# 11_MICROSD.net
KiCad netlist of a schematic drawn in Altium Designer
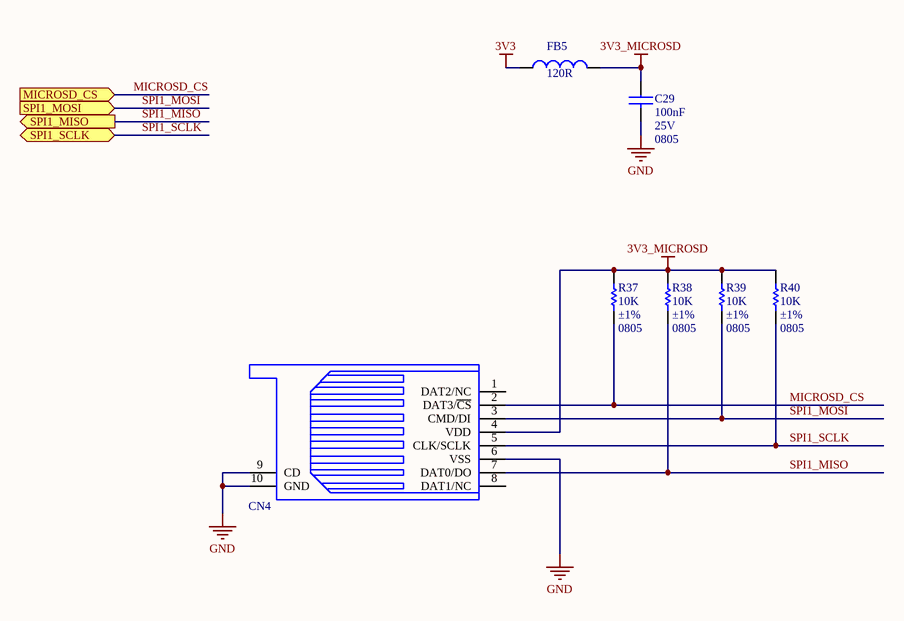
[diagram p0: 11.MICROSD.SchDoc]

(export (version "E")
  (design (tool "Eeschema 10.0.6"))
  (components
    (comp (ref "C29")
      (value "CAP_NP")
      (footprint "CAPC2012X100N_EIA0805")
      (description "CAP CER 0.1UF 25V X7R 0805")
      (fields
        (field (name "PART NUMBER") "SCAP00300093")
        (field (name "CAPACITANCE") "100nF")
        (field (name "TOLERANCE") "±10%")
        (field (name "VOLTAGE - RATED") "25V")
        (field (name "PACKAGE / CASE") "0805")
      )
      (libsource (lib "ComponentDatabase") (part "CAP_NP"))
    )
    (comp (ref "CN4")
      (value "MICRO-SD")
      (footprint "MOLEX_0472192001")
      (description "CONN MICRO SD CARD HINGED TYPE")
      (fields (field (name "PART NUMBER") "SCON00095") (field (name "MANUFACTURER") "Molex, LLC"))
      (libsource (lib "ComponentDatabase") (part "MICRO-SD"))
    )
    (comp (ref "FB5")
      (value "BEAD")
      (footprint "FILC2012X100N_EIA0805")
      (description "FERRITE CHIP POWER 120 OHM SMD")
      (fields
        (field (name "PART NUMBER") "SFIL00005")
        (field (name "IMPEDANCE") "120R")
        (field (name "MANUFACTURER") "Laird-Signal Integrity Products")
      )
      (libsource (lib "ComponentDatabase") (part "BEAD"))
    )
    (comp (ref "R37")
      (value "10K")
      (footprint "RESC2013X65N_EIA0805")
      (description "RES SMD 10K OHM 1% 1/8W 0805")
      (fields
        (field (name "PART NUMBER") "SRES03010098")
        (field (name "TOLERANCE") "±1%")
        (field (name "PACKAGE / CASE") "0805")
        (field (name "MANUFACTURER") "Yageo")
      )
      (libsource (lib "ComponentDatabase") (part "RES"))
    )
    (comp (ref "R38")
      (value "10K")
      (footprint "RESC2013X65N_EIA0805")
      (description "RES SMD 10K OHM 1% 1/8W 0805")
      (fields
        (field (name "PART NUMBER") "SRES03010098")
        (field (name "TOLERANCE") "±1%")
        (field (name "PACKAGE / CASE") "0805")
        (field (name "MANUFACTURER") "Yageo")
      )
      (libsource (lib "ComponentDatabase") (part "RES"))
    )
    (comp (ref "R39")
      (value "10K")
      (footprint "RESC2013X65N_EIA0805")
      (description "RES SMD 10K OHM 1% 1/8W 0805")
      (fields
        (field (name "PART NUMBER") "SRES03010098")
        (field (name "TOLERANCE") "±1%")
        (field (name "PACKAGE / CASE") "0805")
        (field (name "MANUFACTURER") "Yageo")
      )
      (libsource (lib "ComponentDatabase") (part "RES"))
    )
    (comp (ref "R40")
      (value "10K")
      (footprint "RESC2013X65N_EIA0805")
      (description "RES SMD 10K OHM 1% 1/8W 0805")
      (fields
        (field (name "PART NUMBER") "SRES03010098")
        (field (name "TOLERANCE") "±1%")
        (field (name "PACKAGE / CASE") "0805")
        (field (name "MANUFACTURER") "Yageo")
      )
      (libsource (lib "ComponentDatabase") (part "RES"))
    )
  )
  (nets
    (net (code "1") (name "/MICROSD_CS") (class "Default")
      (node (ref "CN4") (pin "2") (pinfunction "DAT3/~{CS}_2") (pintype "passive"))
      (node (ref "R37") (pin "2") (pinfunction "2_2") (pintype "passive"))
    )
    (net (code "2") (name "/SPI1_MISO") (class "Default")
      (node (ref "CN4") (pin "7") (pinfunction "DAT0/DO_7") (pintype "passive"))
      (node (ref "R38") (pin "2") (pinfunction "2_2") (pintype "passive"))
    )
    (net (code "3") (name "/SPI1_MOSI") (class "Default")
      (node (ref "CN4") (pin "3") (pinfunction "CMD/DI_3") (pintype "passive"))
      (node (ref "R39") (pin "2") (pinfunction "2_2") (pintype "passive"))
    )
    (net (code "4") (name "/SPI1_SCLK") (class "Default")
      (node (ref "CN4") (pin "5") (pinfunction "CLK/SCLK_5") (pintype "passive"))
      (node (ref "R40") (pin "2") (pinfunction "2_2") (pintype "passive"))
    )
    (net (code "5") (name "3V3") (class "Default")
      (node (ref "FB5") (pin "1") (pinfunction "1_1") (pintype "passive"))
    )
    (net (code "6") (name "3V3_MICROSD") (class "Default")
      (node (ref "C29") (pin "1") (pinfunction "1_1") (pintype "passive"))
      (node (ref "CN4") (pin "4") (pinfunction "VDD_4") (pintype "passive"))
      (node (ref "FB5") (pin "2") (pinfunction "2_2") (pintype "passive"))
      (node (ref "R37") (pin "1") (pinfunction "1_1") (pintype "passive"))
      (node (ref "R38") (pin "1") (pinfunction "1_1") (pintype "passive"))
      (node (ref "R39") (pin "1") (pinfunction "1_1") (pintype "passive"))
      (node (ref "R40") (pin "1") (pinfunction "1_1") (pintype "passive"))
    )
    (net (code "7") (name "GND") (class "Default")
      (node (ref "C29") (pin "2") (pinfunction "2_2") (pintype "passive"))
      (node (ref "CN4") (pin "10") (pinfunction "GND_10") (pintype "passive"))
      (node (ref "CN4") (pin "6") (pinfunction "VSS_6") (pintype "passive"))
      (node (ref "CN4") (pin "9") (pinfunction "CD_9") (pintype "passive"))
    )
    (net (code "8") (name "unconnected-(CN4-DAT1{slash}NC-Pad8)") (class "Default")
      (node (ref "CN4") (pin "8") (pinfunction "DAT1/NC_8") (pintype "passive"))
    )
    (net (code "9") (name "unconnected-(CN4-DAT2{slash}NC-Pad1)") (class "Default")
      (node (ref "CN4") (pin "1") (pinfunction "DAT2/NC_1") (pintype "passive"))
    )
  )
)
